# Power_Supplies.net
KiCad netlist of a schematic drawn in Altium Designer
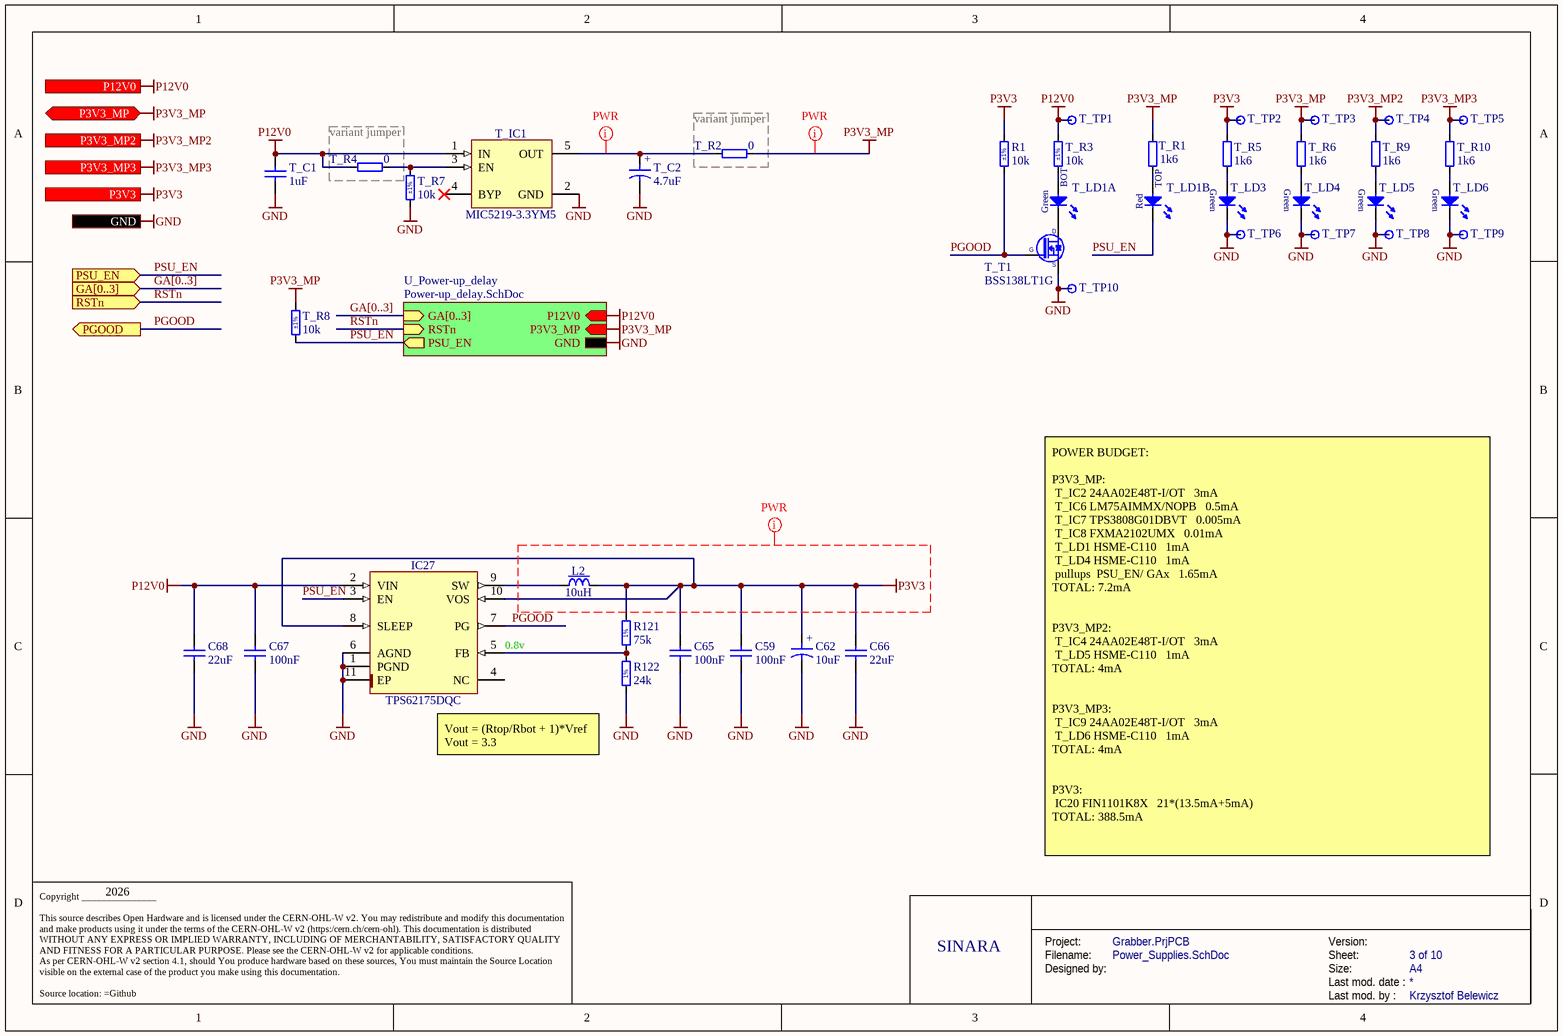
[diagram p0: Power_Supplies.SchDoc]

(export (version "E")
  (design (tool "Eeschema 10.0.6"))
  (components
    (comp (ref "C59")
      (value "100nF")
      (footprint "CAPC1005X55N")
      (description "Non-polarised capacitor")
      (fields
        (field (name "PART NUMBER") "CC0402_100NF_50V_10%_X7R")
        (field (name "VOLTAGE") "50V")
        (field (name "AUTHOR") "CERN DEM MR")
      )
      (libsource (lib "Capacitors") (part "Capacitor - non polarized"))
    )
    (comp (ref "C62")
      (value "10uF")
      (footprint "CAPAE430X540N")
      (description "Polarised capacitor")
      (fields
        (field (name "PART NUMBER") "CAE430-540_10UF_16V_20%")
        (field (name "VOLTAGE") "16V")
        (field (name "AUTHOR") "CERN DEM JLC")
      )
      (libsource (lib "Capacitors") (part "Capacitor - polarized"))
    )
    (comp (ref "C65")
      (value "100nF")
      (footprint "CAPC1005X55N")
      (description "Non-polarised capacitor")
      (fields
        (field (name "PART NUMBER") "CC0402_100NF_50V_10%_X7R")
        (field (name "VOLTAGE") "50V")
        (field (name "AUTHOR") "CERN DEM MR")
      )
      (libsource (lib "Capacitors") (part "Capacitor - non polarized"))
    )
    (comp (ref "C66")
      (value "22uF")
      (footprint "CAPC2012X135N")
      (description "Non-polarised capacitor")
      (fields
        (field (name "PART NUMBER") "CC0805_22UF_16V_10%_X5R")
        (field (name "VOLTAGE") "16V")
        (field (name "AUTHOR") "CERN DEM JLC")
      )
      (libsource (lib "Capacitors") (part "Capacitor - non polarized"))
    )
    (comp (ref "C67")
      (value "100nF")
      (footprint "CAPC1005X55N")
      (description "Non-polarised capacitor")
      (fields
        (field (name "PART NUMBER") "CC0402_100NF_50V_10%_X7R")
        (field (name "VOLTAGE") "50V")
        (field (name "AUTHOR") "CERN DEM MR")
      )
      (libsource (lib "Capacitors") (part "Capacitor - non polarized"))
    )
    (comp (ref "C68")
      (value "22uF")
      (footprint "CAPC2012X135N")
      (description "Non-polarised capacitor")
      (fields
        (field (name "PART NUMBER") "CC0805_22UF_16V_10%_X5R")
        (field (name "VOLTAGE") "16V")
        (field (name "AUTHOR") "CERN DEM JLC")
      )
      (libsource (lib "Capacitors") (part "Capacitor - non polarized"))
    )
    (comp (ref "IC27")
      (value "TPS62175DQC")
      (footprint "SON50P200X300X80-11N-R94X250")
      (description "4.75-28VDC to 1-6VDC, 500mA Step-Down Converter With Sleep Mode")
      (fields (field (name "MANUFACTURER") "TEXAS INSTRUMENTS") (field (name "AUTHOR") "CERN DEM JMW"))
      (libsource (lib "ICs And Semiconductors") (part "TPS62175"))
    )
    (comp (ref "L2")
      (value "10uH")
      (footprint "IND_MURATA-PS_8400")
      (description "Inductor With Core")
      (fields
        (field (name "PART NUMBER") "IND_10UH_10%_MURATA-PS_8400")
        (field (name "POWER") "950mA")
        (field (name "AUTHOR") "CERN DEM JLC")
      )
      (libsource (lib "Inductors & Transformers") (part "Inductor With Magnetic core"))
    )
    (comp (ref "R1")
      (value "10k")
      (footprint "RESC1005X40N")
      (description "Resistor - 1%")
      (fields
        (field (name "TOLERANCE") "±1%")
        (field (name "PART NUMBER") "R0402_10K_1%_0.0625W_100PPM")
        (field (name "POWER") "0.0625W")
        (field (name "AUTHOR") "CERN DEM JLC")
      )
      (libsource (lib "Resistors") (part "Resistor - 1%"))
    )
    (comp (ref "R121")
      (value "75k")
      (footprint "RESC1005X40N")
      (description "Resistor - 1%")
      (fields
        (field (name "PART NUMBER") "R0402_75K_1%_0.0625W_100PPM")
        (field (name "POWER") "0.0625W")
        (field (name "AUTHOR") "CERN DEM JLC")
      )
      (libsource (lib "Resistors") (part "Resistor - 1%"))
    )
    (comp (ref "R122")
      (value "24k")
      (footprint "RESC1005X40N")
      (description "Resistor - 1%")
      (fields
        (field (name "PART NUMBER") "R0402_24K_1%_0.0625W_100PPM")
        (field (name "POWER") "0.0625W")
        (field (name "AUTHOR") "CERN DEM JLC")
      )
      (libsource (lib "Resistors") (part "Resistor - 1%"))
    )
    (comp (ref "T_C1")
      (value "1uF")
      (footprint "CAPC1608X87N")
      (description "Non-polarised capacitor")
      (fields
        (field (name "PART NUMBER") "CC0603_1UF_25V_10%_X7R")
        (field (name "VOLTAGE") "25V")
        (field (name "AUTHOR") "CERN DEM JLC")
      )
      (libsource (lib "Capacitors") (part "Capacitor - non polarized"))
    )
    (comp (ref "T_C2")
      (value "4.7uF")
      (footprint "CAPMP3216X180N")
      (description "Polarised capacitor")
      (fields
        (field (name "PART NUMBER") "CTE3216-18_4.7UF_10V_10%_AVX_TPSA475K010T1400")
        (field (name "VOLTAGE") "10V")
        (field (name "AUTHOR") "CERN DEM JLC")
      )
      (libsource (lib "Capacitors") (part "Capacitor - polarized"))
    )
    (comp (ref "T_IC1")
      (value "MIC5219-3.3YM5")
      (footprint "SOT95P280X145-5N")
      (description "500mA Peak Output LDO Regulator")
      (fields (field (name "MANUFACTURER") "MICROCHIP TECHNOLOGY") (field (name "AUTHOR") "CERN DEM WB"))
      (libsource (lib "ICs And Semiconductors") (part "MIC5219-X.XYM5"))
    )
    (comp (ref "T_LD1")
      (value "Red/Green")
      (footprint "LED_DIALIGHT_571-0112F")
      (description "2x LED  Botom Green, Top Red")
      (fields
        (field (name "PART NUMBER") "LED_DIALIGHT_571-0112F")
        (field (name "MANUFACTURER") "DIALIGHT")
        (field (name "AUTHOR") "CERN DEM JLC")
      )
      (libsource (lib "ICs And Semiconductors") (part "LED x2 G-1C2A-BOT_R-3C4A-TOP"))
    )
    (comp (ref "T_LD3")
      (value "Green")
      (footprint "LED_KINGBRIGHT_KPH-1608CGCK")
      (description "LED Green 1C 2A")
      (fields
        (field (name "PART NUMBER") "LED_KINGBRIGHT_KPH-1608CGCK")
        (field (name "MANUFACTURER") "KINGBRIGHT")
        (field (name "AUTHOR") "CERN DEM JLC")
      )
      (libsource (lib "ICs And Semiconductors") (part "LED Green 1C 2A"))
    )
    (comp (ref "T_LD4")
      (value "Green")
      (footprint "LED_KINGBRIGHT_KPH-1608CGCK")
      (description "LED Green 1C 2A")
      (fields
        (field (name "PART NUMBER") "LED_KINGBRIGHT_KPH-1608CGCK")
        (field (name "MANUFACTURER") "KINGBRIGHT")
        (field (name "AUTHOR") "CERN DEM JLC")
      )
      (libsource (lib "ICs And Semiconductors") (part "LED Green 1C 2A"))
    )
    (comp (ref "T_LD5")
      (value "Green")
      (footprint "LED_KINGBRIGHT_KPH-1608CGCK")
      (description "LED Green 1C 2A")
      (fields
        (field (name "PART NUMBER") "LED_KINGBRIGHT_KPH-1608CGCK")
        (field (name "MANUFACTURER") "KINGBRIGHT")
        (field (name "AUTHOR") "CERN DEM JLC")
      )
      (libsource (lib "ICs And Semiconductors") (part "LED Green 1C 2A"))
    )
    (comp (ref "T_LD6")
      (value "Green")
      (footprint "LED_KINGBRIGHT_KPH-1608CGCK")
      (description "LED Green 1C 2A")
      (fields
        (field (name "PART NUMBER") "LED_KINGBRIGHT_KPH-1608CGCK")
        (field (name "MANUFACTURER") "KINGBRIGHT")
        (field (name "AUTHOR") "CERN DEM JLC")
      )
      (libsource (lib "ICs And Semiconductors") (part "LED Green 1C 2A"))
    )
    (comp (ref "T_R1")
      (value "1k6")
      (footprint "RESC1005X40N")
      (description "Resistor - 1%")
      (fields
        (field (name "PART NUMBER") "R0402_1K6_1%_0.0625W_100PPM")
        (field (name "POWER") "0.0625W")
        (field (name "AUTHOR") "CERN DEM JLC")
      )
      (libsource (lib "Resistors") (part "Resistor - 1%"))
    )
    (comp (ref "T_R2")
      (value "0")
      (footprint "RESC1005X40N")
      (description "Resistor")
      (fields
        (field (name "PART NUMBER") "R0402_0R_JUMPER")
        (field (name "MANUFACTURER") "GENERIC")
        (field (name "AUTHOR") "CERN DEM JLC")
      )
      (libsource (lib "Resistors") (part "Resistor"))
    )
    (comp (ref "T_R3")
      (value "10k")
      (footprint "RESC1005X40N")
      (description "Resistor - 1%")
      (fields
        (field (name "TOLERANCE") "±1%")
        (field (name "PART NUMBER") "R0402_10K_1%_0.0625W_100PPM")
        (field (name "POWER") "0.0625W")
        (field (name "AUTHOR") "CERN DEM JLC")
      )
      (libsource (lib "Resistors") (part "Resistor - 1%"))
    )
    (comp (ref "T_R4")
      (value "0")
      (footprint "RESC1005X40N")
      (description "Resistor")
      (fields
        (field (name "PART NUMBER") "R0402_0R_JUMPER")
        (field (name "MANUFACTURER") "GENERIC")
        (field (name "AUTHOR") "CERN DEM JLC")
      )
      (libsource (lib "Resistors") (part "Resistor"))
    )
    (comp (ref "T_R5")
      (value "1k6")
      (footprint "RESC1005X40N")
      (description "Resistor - 1%")
      (fields
        (field (name "PART NUMBER") "R0402_1K6_1%_0.0625W_100PPM")
        (field (name "POWER") "0.0625W")
        (field (name "AUTHOR") "CERN DEM JLC")
      )
      (libsource (lib "Resistors") (part "Resistor - 1%"))
    )
    (comp (ref "T_R6")
      (value "1k6")
      (footprint "RESC1005X40N")
      (description "Resistor - 1%")
      (fields
        (field (name "PART NUMBER") "R0402_1K6_1%_0.0625W_100PPM")
        (field (name "POWER") "0.0625W")
        (field (name "AUTHOR") "CERN DEM JLC")
      )
      (libsource (lib "Resistors") (part "Resistor - 1%"))
    )
    (comp (ref "T_R7")
      (value "10k")
      (footprint "RESC1005X40N")
      (description "Resistor - 1%")
      (fields
        (field (name "TOLERANCE") "±1%")
        (field (name "PART NUMBER") "R0402_10K_1%_0.0625W_100PPM")
        (field (name "POWER") "0.0625W")
        (field (name "AUTHOR") "CERN DEM JLC")
      )
      (libsource (lib "Resistors") (part "Resistor - 1%"))
    )
    (comp (ref "T_R8")
      (value "10k")
      (footprint "RESC1005X40N")
      (description "Resistor - 1%")
      (fields
        (field (name "TOLERANCE") "±1%")
        (field (name "PART NUMBER") "R0402_10K_1%_0.0625W_100PPM")
        (field (name "POWER") "0.0625W")
        (field (name "AUTHOR") "CERN DEM JLC")
      )
      (libsource (lib "Resistors") (part "Resistor - 1%"))
    )
    (comp (ref "T_R9")
      (value "1k6")
      (footprint "RESC1005X40N")
      (description "Resistor - 1%")
      (fields
        (field (name "PART NUMBER") "R0402_1K6_1%_0.0625W_100PPM")
        (field (name "POWER") "0.0625W")
        (field (name "AUTHOR") "CERN DEM JLC")
      )
      (libsource (lib "Resistors") (part "Resistor - 1%"))
    )
    (comp (ref "T_R10")
      (value "1k6")
      (footprint "RESC1005X40N")
      (description "Resistor - 1%")
      (fields
        (field (name "PART NUMBER") "R0402_1K6_1%_0.0625W_100PPM")
        (field (name "POWER") "0.0625W")
        (field (name "AUTHOR") "CERN DEM JLC")
      )
      (libsource (lib "Resistors") (part "Resistor - 1%"))
    )
    (comp (ref "T_T1")
      (value "BSS138LT1G")
      (footprint "SOT95P240X110-3N")
      (description "N-CHANNEL MOSFET WITH DIODE")
      (fields
        (field (name "MANUFACTURER") "ON SEMICONDUCTOR")
        (field (name "MANUFACTURER PART NUMBER") "BSS138L")
        (field (name "AUTHOR") "CERN DEM JLC")
      )
      (libsource (lib "ICs And Semiconductors") (part "N-MOSFET-D 1G 2S 3D"))
    )
    (comp (ref "T_TP1")
      (value "Test Point")
      (footprint "TPS127")
      (fields (field (name "PART NUMBER") "SMD_PAD_1.27X1.27MM") (field (name "AUTHOR") "CERN DEM JLC"))
      (libsource (lib "Eletro-mechanical") (part "Test Point"))
    )
    (comp (ref "T_TP2")
      (value "Test Point")
      (footprint "TPS127")
      (fields (field (name "PART NUMBER") "SMD_PAD_1.27X1.27MM") (field (name "AUTHOR") "CERN DEM JLC"))
      (libsource (lib "Eletro-mechanical") (part "Test Point"))
    )
    (comp (ref "T_TP3")
      (value "Test Point")
      (footprint "TPS127")
      (fields (field (name "PART NUMBER") "SMD_PAD_1.27X1.27MM") (field (name "AUTHOR") "CERN DEM JLC"))
      (libsource (lib "Eletro-mechanical") (part "Test Point"))
    )
    (comp (ref "T_TP4")
      (value "Test Point")
      (footprint "TPS127")
      (fields (field (name "PART NUMBER") "SMD_PAD_1.27X1.27MM") (field (name "AUTHOR") "CERN DEM JLC"))
      (libsource (lib "Eletro-mechanical") (part "Test Point"))
    )
    (comp (ref "T_TP5")
      (value "Test Point")
      (footprint "TPS127")
      (fields (field (name "PART NUMBER") "SMD_PAD_1.27X1.27MM") (field (name "AUTHOR") "CERN DEM JLC"))
      (libsource (lib "Eletro-mechanical") (part "Test Point"))
    )
    (comp (ref "T_TP6")
      (value "Test Point")
      (footprint "TPS127")
      (fields (field (name "PART NUMBER") "SMD_PAD_1.27X1.27MM") (field (name "AUTHOR") "CERN DEM JLC"))
      (libsource (lib "Eletro-mechanical") (part "Test Point"))
    )
    (comp (ref "T_TP7")
      (value "Test Point")
      (footprint "TPS127")
      (fields (field (name "PART NUMBER") "SMD_PAD_1.27X1.27MM") (field (name "AUTHOR") "CERN DEM JLC"))
      (libsource (lib "Eletro-mechanical") (part "Test Point"))
    )
    (comp (ref "T_TP8")
      (value "Test Point")
      (footprint "TPS127")
      (fields (field (name "PART NUMBER") "SMD_PAD_1.27X1.27MM") (field (name "AUTHOR") "CERN DEM JLC"))
      (libsource (lib "Eletro-mechanical") (part "Test Point"))
    )
    (comp (ref "T_TP9")
      (value "Test Point")
      (footprint "TPS127")
      (fields (field (name "PART NUMBER") "SMD_PAD_1.27X1.27MM") (field (name "AUTHOR") "CERN DEM JLC"))
      (libsource (lib "Eletro-mechanical") (part "Test Point"))
    )
    (comp (ref "T_TP10")
      (value "Test Point")
      (footprint "TPS127")
      (fields (field (name "PART NUMBER") "SMD_PAD_1.27X1.27MM") (field (name "AUTHOR") "CERN DEM JLC"))
      (libsource (lib "Eletro-mechanical") (part "Test Point"))
    )
  )
  (nets
    (net (code "6") (name "/PGOOD") (class "Default")
      (node (ref "IC27") (pin "7") (pinfunction "PG_7") (pintype "output"))
      (node (ref "R1") (pin "1") (pinfunction "1_1") (pintype "passive"))
      (node (ref "T_T1") (pin "1") (pinfunction "G_1") (pintype "passive"))
    )
    (net (code "7") (name "/PSU_EN") (class "Default")
      (node (ref "IC27") (pin "3") (pinfunction "EN_3") (pintype "input"))
      (node (ref "T_LD1") (pin "3") (pinfunction "C_3") (pintype "passive"))
      (node (ref "T_R8") (pin "1") (pinfunction "1_1") (pintype "passive"))
    )
    (net (code "9") (name "GND") (class "Default")
      (node (ref "C59") (pin "1") (pinfunction "1_1") (pintype "passive"))
      (node (ref "C62") (pin "2") (pinfunction "2_2") (pintype "passive"))
      (node (ref "C65") (pin "1") (pinfunction "1_1") (pintype "passive"))
      (node (ref "C66") (pin "1") (pinfunction "1_1") (pintype "passive"))
      (node (ref "C67") (pin "1") (pinfunction "1_1") (pintype "passive"))
      (node (ref "C68") (pin "1") (pinfunction "1_1") (pintype "passive"))
      (node (ref "IC27") (pin "1") (pinfunction "PGND_1") (pintype "power_in"))
      (node (ref "IC27") (pin "11") (pinfunction "EP_11") (pintype "power_in"))
      (node (ref "IC27") (pin "6") (pinfunction "AGND_6") (pintype "power_in"))
      (node (ref "R122") (pin "1") (pinfunction "1_1") (pintype "passive"))
      (node (ref "T_C1") (pin "1") (pinfunction "1_1") (pintype "passive"))
      (node (ref "T_C2") (pin "2") (pinfunction "2_2") (pintype "passive"))
      (node (ref "T_IC1") (pin "2") (pinfunction "GND_2") (pintype "power_in"))
      (node (ref "T_LD3") (pin "1") (pinfunction "C_1") (pintype "passive"))
      (node (ref "T_LD4") (pin "1") (pinfunction "C_1") (pintype "passive"))
      (node (ref "T_LD5") (pin "1") (pinfunction "C_1") (pintype "passive"))
      (node (ref "T_LD6") (pin "1") (pinfunction "C_1") (pintype "passive"))
      (node (ref "T_R7") (pin "1") (pinfunction "1_1") (pintype "passive"))
      (node (ref "T_T1") (pin "2") (pinfunction "S_2") (pintype "passive"))
      (node (ref "T_TP10") (pin "1") (pinfunction "1_1") (pintype "bidirectional"))
      (node (ref "T_TP6") (pin "1") (pinfunction "1_1") (pintype "bidirectional"))
      (node (ref "T_TP7") (pin "1") (pinfunction "1_1") (pintype "bidirectional"))
      (node (ref "T_TP8") (pin "1") (pinfunction "1_1") (pintype "bidirectional"))
      (node (ref "T_TP9") (pin "1") (pinfunction "1_1") (pintype "bidirectional"))
    )
    (net (code "10") (name "Net-(IC27-FB)") (class "Default")
      (node (ref "IC27") (pin "5") (pinfunction "FB_5") (pintype "input"))
      (node (ref "R121") (pin "1") (pinfunction "1_1") (pintype "passive"))
      (node (ref "R122") (pin "2") (pinfunction "2_2") (pintype "passive"))
    )
    (net (code "11") (name "Net-(IC27-SW)") (class "Default")
      (node (ref "IC27") (pin "9") (pinfunction "SW_9") (pintype "output"))
      (node (ref "L2") (pin "1") (pinfunction "1_1") (pintype "passive"))
    )
    (net (code "12") (name "Net-(T_IC1-EN)") (class "Default")
      (node (ref "T_IC1") (pin "3") (pinfunction "EN_3") (pintype "input"))
      (node (ref "T_R4") (pin "2") (pinfunction "2_2") (pintype "passive"))
      (node (ref "T_R7") (pin "2") (pinfunction "2_2") (pintype "passive"))
    )
    (net (code "13") (name "Net-(T_IC1-OUT)") (class "Default")
      (node (ref "T_C2") (pin "1") (pinfunction "1_1") (pintype "passive"))
      (node (ref "T_IC1") (pin "5") (pinfunction "OUT_5") (pintype "power_in"))
      (node (ref "T_R2") (pin "1") (pinfunction "1_1") (pintype "passive"))
    )
    (net (code "14") (name "Net-(T_LD1A-A)") (class "Default")
      (node (ref "T_LD1") (pin "2") (pinfunction "A_2") (pintype "passive"))
      (node (ref "T_R3") (pin "1") (pinfunction "1_1") (pintype "passive"))
    )
    (net (code "15") (name "Net-(T_LD1A-C)") (class "Default")
      (node (ref "T_LD1") (pin "1") (pinfunction "C_1") (pintype "passive"))
      (node (ref "T_T1") (pin "3") (pinfunction "D_3") (pintype "passive"))
    )
    (net (code "16") (name "Net-(T_LD1B-A)") (class "Default")
      (node (ref "T_LD1") (pin "4") (pinfunction "A_4") (pintype "passive"))
      (node (ref "T_R1") (pin "1") (pinfunction "1_1") (pintype "passive"))
    )
    (net (code "17") (name "Net-(T_LD3-A)") (class "Default")
      (node (ref "T_LD3") (pin "2") (pinfunction "A_2") (pintype "passive"))
      (node (ref "T_R5") (pin "1") (pinfunction "1_1") (pintype "passive"))
    )
    (net (code "18") (name "Net-(T_LD4-A)") (class "Default")
      (node (ref "T_LD4") (pin "2") (pinfunction "A_2") (pintype "passive"))
      (node (ref "T_R6") (pin "1") (pinfunction "1_1") (pintype "passive"))
    )
    (net (code "19") (name "Net-(T_LD5-A)") (class "Default")
      (node (ref "T_LD5") (pin "2") (pinfunction "A_2") (pintype "passive"))
      (node (ref "T_R9") (pin "1") (pinfunction "1_1") (pintype "passive"))
    )
    (net (code "20") (name "Net-(T_LD6-A)") (class "Default")
      (node (ref "T_LD6") (pin "2") (pinfunction "A_2") (pintype "passive"))
      (node (ref "T_R10") (pin "1") (pinfunction "1_1") (pintype "passive"))
    )
    (net (code "21") (name "P3V3") (class "Default")
      (node (ref "C59") (pin "2") (pinfunction "2_2") (pintype "passive"))
      (node (ref "C62") (pin "1") (pinfunction "1_1") (pintype "passive"))
      (node (ref "C65") (pin "2") (pinfunction "2_2") (pintype "passive"))
      (node (ref "C66") (pin "2") (pinfunction "2_2") (pintype "passive"))
      (node (ref "IC27") (pin "10") (pinfunction "VOS_10") (pintype "input"))
      (node (ref "IC27") (pin "8") (pinfunction "SLEEP_8") (pintype "input"))
      (node (ref "L2") (pin "2") (pinfunction "2_2") (pintype "passive"))
      (node (ref "R1") (pin "2") (pinfunction "2_2") (pintype "passive"))
      (node (ref "R121") (pin "2") (pinfunction "2_2") (pintype "passive"))
      (node (ref "T_R5") (pin "2") (pinfunction "2_2") (pintype "passive"))
      (node (ref "T_TP2") (pin "1") (pinfunction "1_1") (pintype "bidirectional"))
    )
    (net (code "22") (name "P3V3_MP") (class "Default")
      (node (ref "T_R1") (pin "2") (pinfunction "2_2") (pintype "passive"))
      (node (ref "T_R2") (pin "2") (pinfunction "2_2") (pintype "passive"))
      (node (ref "T_R6") (pin "2") (pinfunction "2_2") (pintype "passive"))
      (node (ref "T_R8") (pin "2") (pinfunction "2_2") (pintype "passive"))
      (node (ref "T_TP3") (pin "1") (pinfunction "1_1") (pintype "bidirectional"))
    )
    (net (code "23") (name "P3V3_MP2") (class "Default")
      (node (ref "T_R9") (pin "2") (pinfunction "2_2") (pintype "passive"))
      (node (ref "T_TP4") (pin "1") (pinfunction "1_1") (pintype "bidirectional"))
    )
    (net (code "24") (name "P3V3_MP3") (class "Default")
      (node (ref "T_R10") (pin "2") (pinfunction "2_2") (pintype "passive"))
      (node (ref "T_TP5") (pin "1") (pinfunction "1_1") (pintype "bidirectional"))
    )
    (net (code "25") (name "P12V0") (class "Default")
      (node (ref "C67") (pin "2") (pinfunction "2_2") (pintype "passive"))
      (node (ref "C68") (pin "2") (pinfunction "2_2") (pintype "passive"))
      (node (ref "IC27") (pin "2") (pinfunction "VIN_2") (pintype "input"))
      (node (ref "T_C1") (pin "2") (pinfunction "2_2") (pintype "passive"))
      (node (ref "T_IC1") (pin "1") (pinfunction "IN_1") (pintype "input"))
      (node (ref "T_R3") (pin "2") (pinfunction "2_2") (pintype "passive"))
      (node (ref "T_R4") (pin "1") (pinfunction "1_1") (pintype "passive"))
      (node (ref "T_TP1") (pin "1") (pinfunction "1_1") (pintype "bidirectional"))
    )
    (net (code "26") (name "unconnected-(IC27-NC-Pad4)") (class "Default")
      (node (ref "IC27") (pin "4") (pinfunction "NC_4") (pintype "passive"))
    )
    (net (code "27") (name "unconnected-(T_IC1-BYP-Pad4)") (class "Default")
      (node (ref "T_IC1") (pin "4") (pinfunction "BYP_4") (pintype "passive+no_connect"))
    )
  )
)
